# BB_analog.net
KiCad netlist of a schematic drawn in Altium Designer
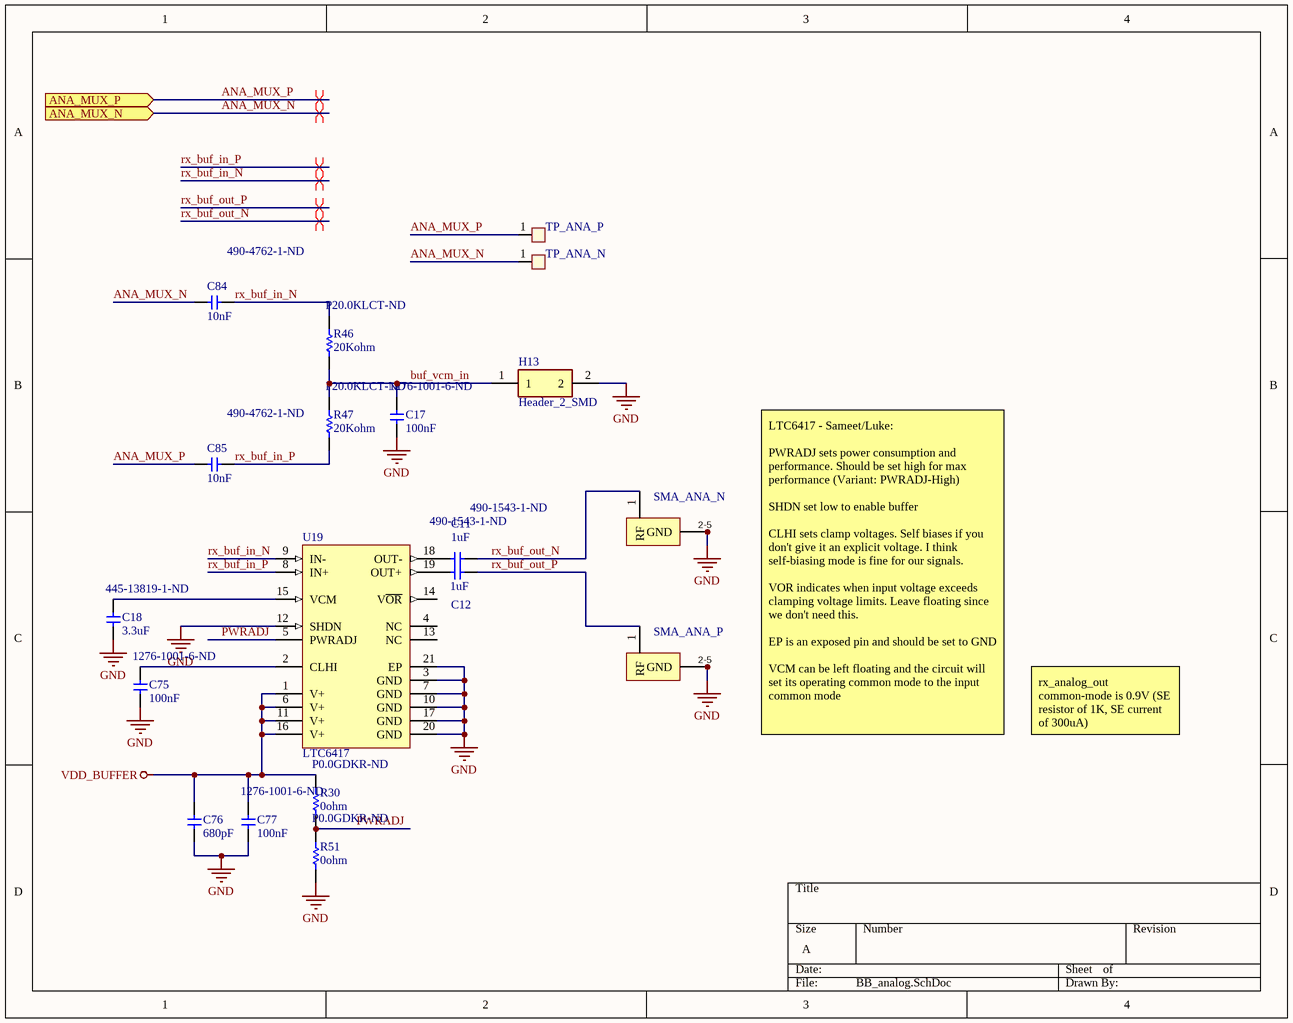
[diagram p0: BB_analog.SchDoc]

(export (version "E")
  (design (tool "Eeschema 10.0.6"))
  (components
    (comp (ref "C11")
      (value "1uF")
      (footprint "CAP_0603")
      (description "CAP CER 1uF 10% 10V X5R 0603")
      (fields (field (name "MANUFACTURER") "Murata") (field (name "SUPPLIER PART NUMBER 1") "490-1543-1-ND"))
      (libsource (lib "fader2_parts") (part "cap 1uF 0603"))
    )
    (comp (ref "C12")
      (value "1uF")
      (footprint "CAP_0603")
      (description "CAP CER 1uF 10% 10V X5R 0603")
      (fields (field (name "MANUFACTURER") "Murata") (field (name "SUPPLIER PART NUMBER 1") "490-1543-1-ND"))
      (libsource (lib "fader2_parts") (part "cap 1uF 0603"))
    )
    (comp (ref "C17")
      (value "100nF")
      (footprint "CAP_0402")
      (description "CAP CER 0.1uF 10% 16V X7R 0402")
      (fields
        (field (name "MANUFACTURER") "Samsung Electro-Mechanics")
        (field (name "SUPPLIER PART NUMBER 1") "1276-1001-6-ND")
      )
      (libsource (lib "fader2_parts") (part "cap 100nF"))
    )
    (comp (ref "C18")
      (value "3.3uF")
      (footprint "CAP_0402")
      (description "CAP CER 3.3uF 10% 10V X5R 0402")
      (fields (field (name "MANUFACTURER") "TDK") (field (name "SUPPLIER PART NUMBER 1") "445-13819-1-ND"))
      (libsource (lib "fader2_parts") (part "cap 3p3uF"))
    )
    (comp (ref "C75")
      (value "100nF")
      (footprint "CAP_0402")
      (description "CAP CER 0.1uF 10% 16V X7R 0402")
      (fields
        (field (name "MANUFACTURER") "Samsung Electro-Mechanics")
        (field (name "SUPPLIER PART NUMBER 1") "1276-1001-6-ND")
      )
      (libsource (lib "fader2_parts") (part "cap 100nF"))
    )
    (comp (ref "C76")
      (value "680pF")
      (footprint "CAP_0603")
      (description "CAP CER 680pF 5% 25V C0G/NP0 0603")
      (fields (field (name "MANUFACTURER") "Kemet"))
      (libsource (lib "fader2_parts") (part "cap 680pF 0603"))
    )
    (comp (ref "C77")
      (value "100nF")
      (footprint "CAP_0402")
      (description "CAP CER 0.1uF 10% 16V X7R 0402")
      (fields
        (field (name "MANUFACTURER") "Samsung Electro-Mechanics")
        (field (name "SUPPLIER PART NUMBER 1") "1276-1001-6-ND")
      )
      (libsource (lib "fader2_parts") (part "cap 100nF"))
    )
    (comp (ref "C84")
      (value "10nF")
      (footprint "CAPC1005X06L_HD")
      (description "CAP CER 10nF 10% 50V X7R 0402")
      (fields (field (name "MANUFACTURER") "Murata") (field (name "SUPPLIER PART NUMBER 1") "490-4762-1-ND"))
      (libsource (lib "fader2_parts") (part "cap 10nF"))
    )
    (comp (ref "C85")
      (value "10nF")
      (footprint "CAPC1005X06L_HD")
      (description "CAP CER 10nF 10% 50V X7R 0402")
      (fields (field (name "MANUFACTURER") "Murata") (field (name "SUPPLIER PART NUMBER 1") "490-4762-1-ND"))
      (libsource (lib "fader2_parts") (part "cap 10nF"))
    )
    (comp (ref "H13")
      (value "Header_2_SMD")
      (footprint "HDR1X2_SMD_S")
      (description "Connector Header Vertical, SMD, 2 position 0.100\" (2.54mm)")
      (fields
        (field (name "MANUFACTURER_PART_NUMBER") "TSM-102-01-S-SV")
        (field (name "MOUSER PART NUMBER") "200-TSM10201SSV")
      )
      (libsource (lib "fader2_parts") (part "Header_2_SMD"))
    )
    (comp (ref "R30")
      (value "0ohm")
      (footprint "RES_0603")
      (description "RES SMD 0 OHM JUMPER 1/10W 0603")
      (fields (field (name "MANUFACTURER") "Panasonic") (field (name "SUPPLIER PART NUMBER 1") "P0.0GDKR-ND"))
      (libsource (lib "fader2_parts") (part "res 0 ohm 0603"))
    )
    (comp (ref "R46")
      (value "20Kohm")
      (footprint "RES_0402")
      (description "RES SMD 20k OHM 1% 1/10W 0402")
      (fields
        (field (name "MANUFACTURER") "Panasonic")
        (field (name "SUPPLIER PART NUMBER 1") "P20.0KLCT-ND")
      )
      (libsource (lib "fader2_parts") (part "res 20 Kohm"))
    )
    (comp (ref "R47")
      (value "20Kohm")
      (footprint "RES_0402")
      (description "RES SMD 20k OHM 1% 1/10W 0402")
      (fields
        (field (name "MANUFACTURER") "Panasonic")
        (field (name "SUPPLIER PART NUMBER 1") "P20.0KLCT-ND")
      )
      (libsource (lib "fader2_parts") (part "res 20 Kohm"))
    )
    (comp (ref "R51")
      (value "0ohm")
      (footprint "RES_0603")
      (description "RES SMD 0 OHM JUMPER 1/10W 0603")
      (fields (field (name "MANUFACTURER") "Panasonic") (field (name "SUPPLIER PART NUMBER 1") "P0.0GDKR-ND"))
      (libsource (lib "fader2_parts") (part "res 0 ohm 0603"))
    )
    (comp (ref "SMA_ANA_N")
      (value "CONSMA001-SMD-G")
      (footprint "CON-SMA-SMD")
      (description "SMD SMA CONNECTOR")
      (libsource (lib "fader2_parts") (part "SURFACE MOUNT SMA CONNECTOR"))
    )
    (comp (ref "SMA_ANA_P")
      (value "CONSMA001-SMD-G")
      (footprint "CON-SMA-SMD")
      (description "SMD SMA CONNECTOR")
      (libsource (lib "fader2_parts") (part "SURFACE MOUNT SMA CONNECTOR"))
    )
    (comp (ref "TP_ANA_N")
      (value "TestPoint_SMD")
      (footprint "TestPoint_SMD")
      (description "Test Point, SMD 1mm x 1.8mm, 1.15mm high.")
      (libsource (lib "fader2_parts") (part "TestPoint_SMD"))
    )
    (comp (ref "TP_ANA_P")
      (value "TestPoint_SMD")
      (footprint "TestPoint_SMD")
      (description "Test Point, SMD 1mm x 1.8mm, 1.15mm high.")
      (libsource (lib "fader2_parts") (part "TestPoint_SMD"))
    )
    (comp (ref "U19")
      (value "LTC6417")
      (footprint "LT-UDC-20_N_NPV")
      (fields (field (name "MANUFACTURER") "Linear Technology") (field (name "PARTNUMBER") "LTC6417CUDC#PBF"))
      (libsource (lib "fader2_parts") (part "LTC6417CUDC#PBF"))
    )
  )
  (nets
    (net (code "1") (name "/ANA_MUX_N") (class "Default")
      (node (ref "C84") (pin "1") (pinfunction "1_1") (pintype "passive"))
      (node (ref "TP_ANA_N") (pin "1") (pinfunction "TP_1") (pintype "passive"))
    )
    (net (code "2") (name "/ANA_MUX_P") (class "Default")
      (node (ref "C85") (pin "1") (pinfunction "1_1") (pintype "passive"))
      (node (ref "TP_ANA_P") (pin "1") (pinfunction "TP_1") (pintype "passive"))
    )
    (net (code "3") (name "/PWRADJ") (class "Default")
      (node (ref "R30") (pin "2") (pinfunction "BOT_2") (pintype "passive"))
      (node (ref "R51") (pin "1") (pinfunction "TOP_1") (pintype "passive"))
      (node (ref "U19") (pin "5") (pinfunction "PWRADJ_5") (pintype "power_in"))
    )
    (net (code "4") (name "/buf_vcm_in") (class "Default")
      (node (ref "C17") (pin "1") (pinfunction "1_1") (pintype "passive"))
      (node (ref "H13") (pin "1") (pinfunction "1_1") (pintype "passive"))
      (node (ref "R46") (pin "2") (pinfunction "BOT_2") (pintype "passive"))
      (node (ref "R47") (pin "1") (pinfunction "TOP_1") (pintype "passive"))
    )
    (net (code "5") (name "/rx_buf_in_N") (class "Default")
      (node (ref "C84") (pin "2") (pinfunction "2_2") (pintype "passive"))
      (node (ref "R46") (pin "1") (pinfunction "TOP_1") (pintype "passive"))
      (node (ref "U19") (pin "9") (pinfunction "IN-_9") (pintype "input"))
    )
    (net (code "6") (name "/rx_buf_in_P") (class "Default")
      (node (ref "C85") (pin "2") (pinfunction "2_2") (pintype "passive"))
      (node (ref "R47") (pin "2") (pinfunction "BOT_2") (pintype "passive"))
      (node (ref "U19") (pin "8") (pinfunction "IN+_8") (pintype "input"))
    )
    (net (code "7") (name "/rx_buf_out_N") (class "Default")
      (node (ref "C11") (pin "2") (pinfunction "2_2") (pintype "passive"))
      (node (ref "SMA_ANA_N") (pin "1") (pinfunction "RF_1") (pintype "passive"))
    )
    (net (code "8") (name "/rx_buf_out_P") (class "Default")
      (node (ref "C12") (pin "1") (pinfunction "1_1") (pintype "passive"))
      (node (ref "SMA_ANA_P") (pin "1") (pinfunction "RF_1") (pintype "passive"))
    )
    (net (code "9") (name "GND") (class "Default")
      (node (ref "C17") (pin "2") (pinfunction "2_2") (pintype "passive"))
      (node (ref "C18") (pin "2") (pinfunction "2_2") (pintype "passive"))
      (node (ref "C75") (pin "2") (pinfunction "2_2") (pintype "passive"))
      (node (ref "C76") (pin "2") (pinfunction "2_2") (pintype "passive"))
      (node (ref "C77") (pin "2") (pinfunction "2_2") (pintype "passive"))
      (node (ref "H13") (pin "2") (pinfunction "2_2") (pintype "passive"))
      (node (ref "R51") (pin "2") (pinfunction "BOT_2") (pintype "passive"))
      (node (ref "SMA_ANA_N") (pin "2") (pinfunction "GND_2") (pintype "passive"))
      (node (ref "SMA_ANA_N") (pin "3") (pinfunction "GND_3") (pintype "passive"))
      (node (ref "SMA_ANA_N") (pin "4") (pinfunction "GND_4") (pintype "passive"))
      (node (ref "SMA_ANA_N") (pin "5") (pinfunction "GND_5") (pintype "passive"))
      (node (ref "SMA_ANA_P") (pin "2") (pinfunction "GND_2") (pintype "passive"))
      (node (ref "SMA_ANA_P") (pin "3") (pinfunction "GND_3") (pintype "passive"))
      (node (ref "SMA_ANA_P") (pin "4") (pinfunction "GND_4") (pintype "passive"))
      (node (ref "SMA_ANA_P") (pin "5") (pinfunction "GND_5") (pintype "passive"))
      (node (ref "U19") (pin "10") (pinfunction "GND_10") (pintype "power_in"))
      (node (ref "U19") (pin "12") (pinfunction "SHDN_12") (pintype "input"))
      (node (ref "U19") (pin "17") (pinfunction "GND_17") (pintype "power_in"))
      (node (ref "U19") (pin "20") (pinfunction "GND_20") (pintype "power_in"))
      (node (ref "U19") (pin "21") (pinfunction "EP_21") (pintype "power_in"))
      (node (ref "U19") (pin "3") (pinfunction "GND_3") (pintype "power_in"))
      (node (ref "U19") (pin "7") (pinfunction "GND_7") (pintype "power_in"))
    )
    (net (code "10") (name "Net-(U19-CLHI)") (class "Default")
      (node (ref "C75") (pin "1") (pinfunction "1_1") (pintype "passive"))
      (node (ref "U19") (pin "2") (pinfunction "CLHI_2") (pintype "power_in"))
    )
    (net (code "11") (name "Net-(U19-OUT+)") (class "Default")
      (node (ref "C12") (pin "2") (pinfunction "2_2") (pintype "passive"))
      (node (ref "U19") (pin "19") (pinfunction "OUT+_19") (pintype "output"))
    )
    (net (code "12") (name "Net-(U19-OUT-)") (class "Default")
      (node (ref "C11") (pin "1") (pinfunction "1_1") (pintype "passive"))
      (node (ref "U19") (pin "18") (pinfunction "OUT-_18") (pintype "output"))
    )
    (net (code "13") (name "Net-(U19-VCM)") (class "Default")
      (node (ref "C18") (pin "1") (pinfunction "1_1") (pintype "passive"))
      (node (ref "U19") (pin "15") (pinfunction "VCM_15") (pintype "input"))
    )
    (net (code "14") (name "VDD_BUFFER") (class "Default")
      (node (ref "C76") (pin "1") (pinfunction "1_1") (pintype "passive"))
      (node (ref "C77") (pin "1") (pinfunction "1_1") (pintype "passive"))
      (node (ref "R30") (pin "1") (pinfunction "TOP_1") (pintype "passive"))
      (node (ref "U19") (pin "1") (pinfunction "V+_1") (pintype "power_in"))
      (node (ref "U19") (pin "11") (pinfunction "V+_11") (pintype "power_in"))
      (node (ref "U19") (pin "16") (pinfunction "V+_16") (pintype "power_in"))
      (node (ref "U19") (pin "6") (pinfunction "V+_6") (pintype "power_in"))
    )
    (net (code "15") (name "unconnected-(U19-NC-Pad4)") (class "Default")
      (node (ref "U19") (pin "4") (pinfunction "NC_4") (pintype "passive"))
    )
    (net (code "16") (name "unconnected-(U19-NC-Pad13)") (class "Default")
      (node (ref "U19") (pin "13") (pinfunction "NC_13") (pintype "passive"))
    )
    (net (code "17") (name "unconnected-(U19-V~{OR}-Pad14)") (class "Default")
      (node (ref "U19") (pin "14") (pinfunction "V~{OR}_14") (pintype "output"))
    )
  )
)
